# source_wifi.net
KiCad netlist of a schematic drawn in EAGLE
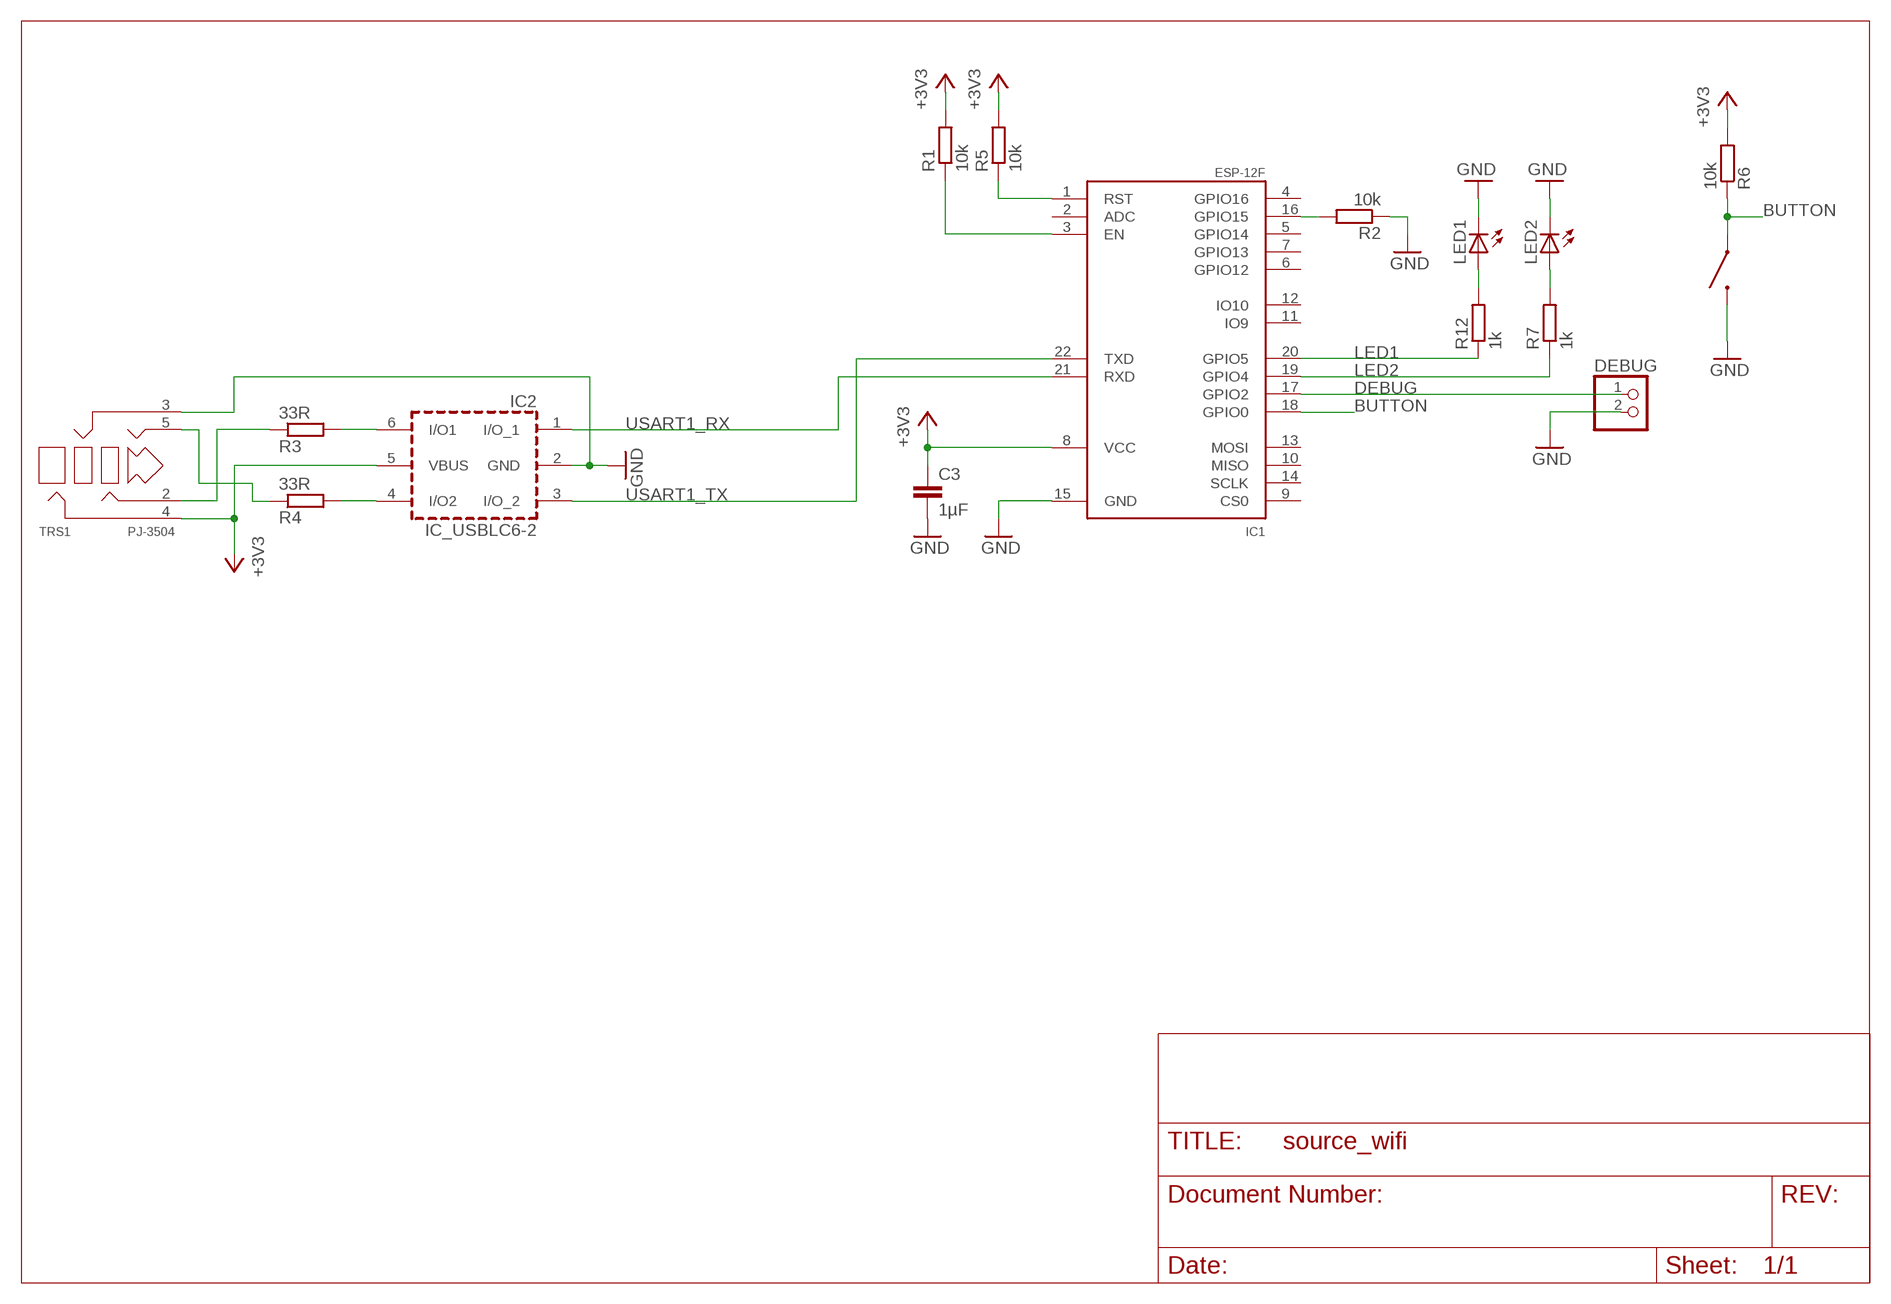
[diagram p0: schematic, sheet 1]

(export (version "E")
  (design (tool "Eeschema 10.0.6"))
  (components
    (comp (ref "C3")
      (value "1µF")
      (footprint "eagle-import:C0603")
      (libsource (lib "eagle-import") (part "C-EUC0603"))
    )
    (comp (ref "DEBUG")
      (value "HEADER-1X2ROUND")
      (footprint "eagle-import:1X02_ROUND")
      (libsource (lib "eagle-import") (part "HEADER-1X2ROUND"))
    )
    (comp (ref "IC1")
      (value "ESP-12F")
      (footprint "eagle-import:ESP-12F")
      (libsource (lib "eagle-import") (part "ESP-12F"))
    )
    (comp (ref "IC2")
      (value "IC_USBLC6-2")
      (footprint "eagle-import:SOT-23-6L")
      (libsource (lib "eagle-import") (part "IC_USBLC6-2"))
    )
    (comp (ref "ISP")
      (value "TACT-SWITCH-40-40")
      (footprint "eagle-import:40-40")
      (libsource (lib "eagle-import") (part "TACT-SWITCH-40-40"))
    )
    (comp (ref "LED1")
      (value "LEDCHIP-LED0603")
      (footprint "eagle-import:CHIP-LED0603")
      (libsource (lib "eagle-import") (part "LEDCHIP-LED0603"))
    )
    (comp (ref "LED2")
      (value "LEDCHIP-LED0603")
      (footprint "eagle-import:CHIP-LED0603")
      (libsource (lib "eagle-import") (part "LEDCHIP-LED0603"))
    )
    (comp (ref "R1")
      (value "10k")
      (footprint "eagle-import:R0603")
      (libsource (lib "eagle-import") (part "R-EU_R0603"))
    )
    (comp (ref "R2")
      (value "10k")
      (footprint "eagle-import:R0603")
      (libsource (lib "eagle-import") (part "R-EU_R0603"))
    )
    (comp (ref "R3")
      (value "33R")
      (footprint "eagle-import:R0603")
      (libsource (lib "eagle-import") (part "R-EU_R0603"))
    )
    (comp (ref "R4")
      (value "33R")
      (footprint "eagle-import:R0603")
      (libsource (lib "eagle-import") (part "R-EU_R0603"))
    )
    (comp (ref "R5")
      (value "10k")
      (footprint "eagle-import:R0603")
      (libsource (lib "eagle-import") (part "R-EU_R0603"))
    )
    (comp (ref "R6")
      (value "10k")
      (footprint "eagle-import:R0603")
      (libsource (lib "eagle-import") (part "R-EU_R0603"))
    )
    (comp (ref "R7")
      (value "1k")
      (footprint "eagle-import:R0603")
      (libsource (lib "eagle-import") (part "R-EU_R0603"))
    )
    (comp (ref "R12")
      (value "1k")
      (footprint "eagle-import:R0603")
      (libsource (lib "eagle-import") (part "R-EU_R0603"))
    )
    (comp (ref "TRS1")
      (value "PJ-3504")
      (footprint "eagle-import:YD-PJ-3504")
      (libsource (lib "eagle-import") (part "PJ-3504"))
    )
  )
  (nets
    (net (code "1") (name "+3V3") (class "Default")
      (node (ref "C3") (pin "1") (pinfunction "1_1") (pintype "passive"))
      (node (ref "IC1") (pin "8") (pinfunction "VCC_8") (pintype "bidirectional"))
      (node (ref "IC2") (pin "5") (pinfunction "VBUS_5") (pintype "bidirectional"))
      (node (ref "R1") (pin "2") (pinfunction "2_2") (pintype "passive"))
      (node (ref "R5") (pin "2") (pinfunction "2_2") (pintype "passive"))
      (node (ref "R6") (pin "2") (pinfunction "2_2") (pintype "passive"))
      (node (ref "TRS1") (pin "4") (pinfunction "4_4") (pintype "bidirectional"))
    )
    (net (code "2") (name "/BUTTON") (class "Default")
      (node (ref "IC1") (pin "18") (pinfunction "GPIO0_18") (pintype "bidirectional"))
      (node (ref "ISP") (pin "3") (pinfunction "P$2_3") (pintype "bidirectional"))
      (node (ref "ISP") (pin "4") (pinfunction "P$2_4") (pintype "bidirectional"))
      (node (ref "R6") (pin "1") (pinfunction "1_1") (pintype "passive"))
    )
    (net (code "3") (name "/DEBUG") (class "Default")
      (node (ref "DEBUG") (pin "1") (pinfunction "1_1") (pintype "passive"))
      (node (ref "IC1") (pin "17") (pinfunction "GPIO2_17") (pintype "bidirectional"))
    )
    (net (code "4") (name "/LED1") (class "Default")
      (node (ref "IC1") (pin "20") (pinfunction "GPIO5_20") (pintype "bidirectional"))
      (node (ref "R12") (pin "1") (pinfunction "1_1") (pintype "passive"))
    )
    (net (code "5") (name "/LED2") (class "Default")
      (node (ref "IC1") (pin "19") (pinfunction "GPIO4_19") (pintype "bidirectional"))
      (node (ref "R7") (pin "1") (pinfunction "1_1") (pintype "passive"))
    )
    (net (code "6") (name "/USART1_RX") (class "Default")
      (node (ref "IC1") (pin "21") (pinfunction "RXD_21") (pintype "bidirectional"))
      (node (ref "IC2") (pin "1") (pinfunction "I/O_1_1") (pintype "bidirectional"))
    )
    (net (code "7") (name "/USART1_TX") (class "Default")
      (node (ref "IC1") (pin "22") (pinfunction "TXD_22") (pintype "bidirectional"))
      (node (ref "IC2") (pin "3") (pinfunction "I/O_2_3") (pintype "bidirectional"))
    )
    (net (code "8") (name "GND") (class "Default")
      (node (ref "C3") (pin "2") (pinfunction "2_2") (pintype "passive"))
      (node (ref "DEBUG") (pin "2") (pinfunction "2_2") (pintype "passive"))
      (node (ref "IC1") (pin "15") (pinfunction "GND_15") (pintype "bidirectional"))
      (node (ref "IC2") (pin "2") (pinfunction "GND_2") (pintype "bidirectional"))
      (node (ref "ISP") (pin "1") (pinfunction "P$1_1") (pintype "bidirectional"))
      (node (ref "ISP") (pin "2") (pinfunction "P$1_2") (pintype "bidirectional"))
      (node (ref "LED1") (pin "C") (pinfunction "C_C") (pintype "passive"))
      (node (ref "LED2") (pin "C") (pinfunction "C_C") (pintype "passive"))
      (node (ref "R2") (pin "1") (pinfunction "1_1") (pintype "passive"))
      (node (ref "TRS1") (pin "3") (pinfunction "3_3") (pintype "bidirectional"))
    )
    (net (code "9") (name "Net-(IC1-EN)") (class "Default")
      (node (ref "IC1") (pin "3") (pinfunction "EN_3") (pintype "bidirectional"))
      (node (ref "R1") (pin "1") (pinfunction "1_1") (pintype "passive"))
    )
    (net (code "10") (name "Net-(IC1-GPIO15)") (class "Default")
      (node (ref "IC1") (pin "16") (pinfunction "GPIO15_16") (pintype "bidirectional"))
      (node (ref "R2") (pin "2") (pinfunction "2_2") (pintype "passive"))
    )
    (net (code "11") (name "Net-(IC1-RST)") (class "Default")
      (node (ref "IC1") (pin "1") (pinfunction "RST_1") (pintype "bidirectional"))
      (node (ref "R5") (pin "1") (pinfunction "1_1") (pintype "passive"))
    )
    (net (code "12") (name "Net-(IC2-I{slash}O1)") (class "Default")
      (node (ref "IC2") (pin "6") (pinfunction "I/O1_6") (pintype "bidirectional"))
      (node (ref "R3") (pin "2") (pinfunction "2_2") (pintype "passive"))
    )
    (net (code "13") (name "Net-(IC2-I{slash}O2)") (class "Default")
      (node (ref "IC2") (pin "4") (pinfunction "I/O2_4") (pintype "bidirectional"))
      (node (ref "R4") (pin "2") (pinfunction "2_2") (pintype "passive"))
    )
    (net (code "14") (name "Net-(LED1-PadA)") (class "Default")
      (node (ref "LED1") (pin "A") (pinfunction "A_A") (pintype "passive"))
      (node (ref "R12") (pin "2") (pinfunction "2_2") (pintype "passive"))
    )
    (net (code "15") (name "Net-(LED2-PadA)") (class "Default")
      (node (ref "LED2") (pin "A") (pinfunction "A_A") (pintype "passive"))
      (node (ref "R7") (pin "2") (pinfunction "2_2") (pintype "passive"))
    )
    (net (code "16") (name "Net-(R3-Pad1)") (class "Default")
      (node (ref "R3") (pin "1") (pinfunction "1_1") (pintype "passive"))
      (node (ref "TRS1") (pin "2") (pinfunction "2_2") (pintype "bidirectional"))
    )
    (net (code "17") (name "Net-(R4-Pad1)") (class "Default")
      (node (ref "R4") (pin "1") (pinfunction "1_1") (pintype "passive"))
      (node (ref "TRS1") (pin "5") (pinfunction "5_5") (pintype "bidirectional"))
    )
    (net (code "18") (name "unconnected-(IC1-ADC-Pad2)") (class "Default")
      (node (ref "IC1") (pin "2") (pinfunction "ADC_2") (pintype "bidirectional"))
    )
    (net (code "19") (name "unconnected-(IC1-CS0-Pad9)") (class "Default")
      (node (ref "IC1") (pin "9") (pinfunction "CS0_9") (pintype "bidirectional"))
    )
    (net (code "20") (name "unconnected-(IC1-GPIO12-Pad6)") (class "Default")
      (node (ref "IC1") (pin "6") (pinfunction "GPIO12_6") (pintype "bidirectional"))
    )
    (net (code "21") (name "unconnected-(IC1-GPIO13-Pad7)") (class "Default")
      (node (ref "IC1") (pin "7") (pinfunction "GPIO13_7") (pintype "bidirectional"))
    )
    (net (code "22") (name "unconnected-(IC1-GPIO14-Pad5)") (class "Default")
      (node (ref "IC1") (pin "5") (pinfunction "GPIO14_5") (pintype "bidirectional"))
    )
    (net (code "23") (name "unconnected-(IC1-GPIO16-Pad4)") (class "Default")
      (node (ref "IC1") (pin "4") (pinfunction "GPIO16_4") (pintype "bidirectional"))
    )
    (net (code "24") (name "unconnected-(IC1-IO9-Pad11)") (class "Default")
      (node (ref "IC1") (pin "11") (pinfunction "IO9_11") (pintype "bidirectional"))
    )
    (net (code "25") (name "unconnected-(IC1-IO10-Pad12)") (class "Default")
      (node (ref "IC1") (pin "12") (pinfunction "IO10_12") (pintype "bidirectional"))
    )
    (net (code "26") (name "unconnected-(IC1-MISO-Pad10)") (class "Default")
      (node (ref "IC1") (pin "10") (pinfunction "MISO_10") (pintype "bidirectional"))
    )
    (net (code "27") (name "unconnected-(IC1-MOSI-Pad13)") (class "Default")
      (node (ref "IC1") (pin "13") (pinfunction "MOSI_13") (pintype "bidirectional"))
    )
    (net (code "28") (name "unconnected-(IC1-SCLK-Pad14)") (class "Default")
      (node (ref "IC1") (pin "14") (pinfunction "SCLK_14") (pintype "bidirectional"))
    )
  )
)
